# RcMPPT-Power_Module.net
KiCad netlist of a schematic drawn in Altium Designer
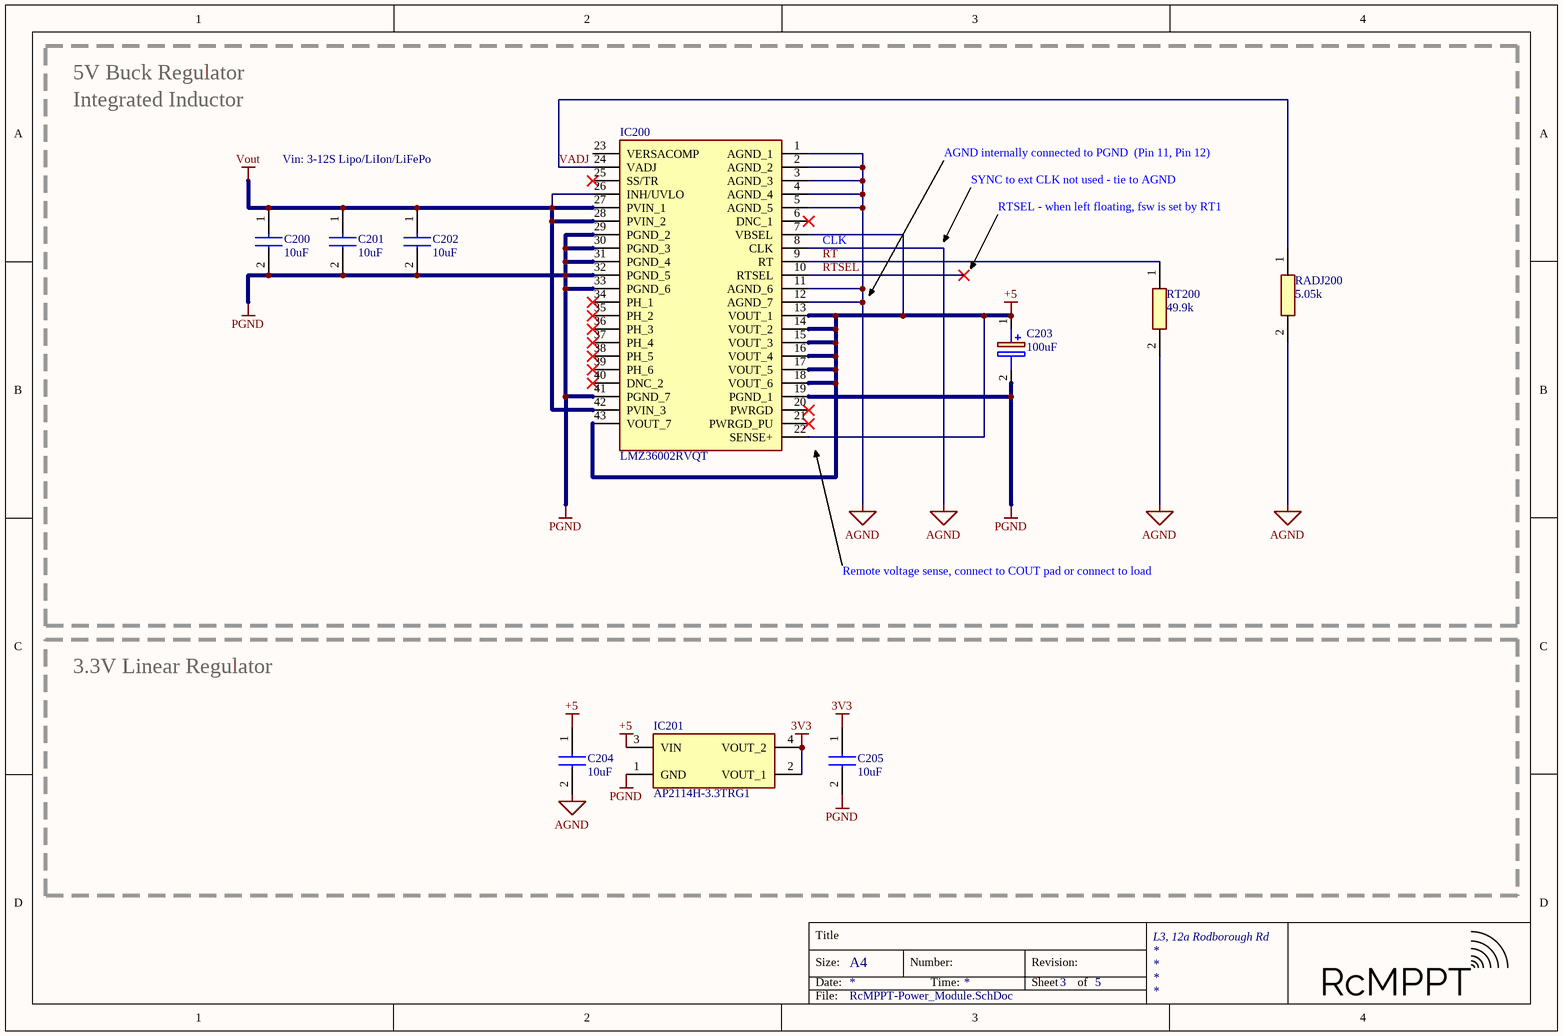
[diagram p0: RcMPPT-Power_Module.SchDoc]

(export (version "E")
  (design (tool "Eeschema 10.0.6"))
  (components
    (comp (ref "C200")
      (value "10uF")
      (footprint "RcMPPTLib:CAPC3225X280N")
      (description "Capacitor")
      (fields (field (name "MANUFACTURER_PART_NUMBER") "CL32B106KMVNNWE"))
      (libsource (lib "RcMPPTLib") (part "CL32B106KMVNNWE"))
    )
    (comp (ref "C201")
      (value "10uF")
      (footprint "RcMPPTLib:CAPC3225X280N")
      (description "Capacitor")
      (fields (field (name "MANUFACTURER_PART_NUMBER") "CL32B106KMVNNWE"))
      (libsource (lib "RcMPPTLib") (part "CL32B106KMVNNWE"))
    )
    (comp (ref "C202")
      (value "10uF")
      (footprint "RcMPPTLib:CAPC3225X280N")
      (description "Capacitor")
      (fields (field (name "MANUFACTURER_PART_NUMBER") "CL32B106KMVNNWE"))
      (libsource (lib "RcMPPTLib") (part "CL32B106KMVNNWE"))
    )
    (comp (ref "C203")
      (value "100uF")
      (footprint "CAPPM3528X200N")
      (description "Capacitor Polarised")
      (fields
        (field (name "MANUFACTURER_PART_NUMBER") "8TPE100MAZB")
        (field (name "MOUSER PART NUMBER") "667-8TPE100MAZB")
      )
      (libsource (lib "RcMPPTLib") (part "8TPE100MAZB"))
    )
    (comp (ref "C204")
      (value "10uF")
      (footprint "RcMPPTLib:CAPC3225X280N")
      (description "Capacitor")
      (fields (field (name "MANUFACTURER_PART_NUMBER") "CL32B106KMVNNWE"))
      (libsource (lib "RcMPPTLib") (part "CL32B106KMVNNWE"))
    )
    (comp (ref "C205")
      (value "10uF")
      (footprint "RcMPPTLib:CAPC3225X280N")
      (description "Capacitor")
      (fields (field (name "MANUFACTURER_PART_NUMBER") "CL32B106KMVNNWE"))
      (libsource (lib "RcMPPTLib") (part "CL32B106KMVNNWE"))
    )
    (comp (ref "IC200")
      (value "LMZ36002RVQT")
      (footprint "LMZ36002RVQR")
      (description "Integrated Circuit")
      (fields (field (name "MOUSER PART NUMBER") "595-LMZ36002RVQT"))
      (libsource (lib "RcMPPTLib") (part "LMZ36002RVQT"))
    )
    (comp (ref "IC201")
      (value "AP2114H-3.3TRG1")
      (footprint "SOT230P700X180-4N")
      (description "Integrated Circuit")
      (fields (field (name "MOUSER PART NUMBER") "621-AP2114H-3.3TRG1"))
      (libsource (lib "RcMPPTLib") (part "AP2114H-3.3TRG1"))
    )
    (comp (ref "RADJ200")
      (value "5.05k")
      (footprint "R0805")
      (description "Resistor")
      (fields
        (field (name "MANUFACTURER_PART_NUMBER") "RT0805BRD075K05L")
        (field (name "MOUSER PART NUMBER") "603-RT0805BRD075K05L")
      )
      (libsource (lib "RcMPPTLib") (part "RT0805BRD075K05L"))
    )
    (comp (ref "RT200")
      (value "49.9k")
      (footprint "RcMPPTLib:R0805")
      (description "Resistor")
      (fields
        (field (name "MANUFACTURER_PART_NUMBER") "ERJ-6ENF4992V")
        (field (name "MOUSER PART NUMBER") "667-ERJ-6ENF4992V")
      )
      (libsource (lib "RcMPPTLib") (part "ERJ-6ENF4992V"))
    )
  )
  (nets
    (net (code "1") (name "+5") (class "Default")
      (node (ref "C203") (pin "1") (pinfunction "+_1") (pintype "passive"))
      (node (ref "C204") (pin "1") (pinfunction "1_1") (pintype "passive"))
      (node (ref "IC200") (pin "13") (pinfunction "VOUT_1_13") (pintype "passive"))
      (node (ref "IC200") (pin "14") (pinfunction "VOUT_2_14") (pintype "passive"))
      (node (ref "IC200") (pin "15") (pinfunction "VOUT_3_15") (pintype "passive"))
      (node (ref "IC200") (pin "16") (pinfunction "VOUT_4_16") (pintype "passive"))
      (node (ref "IC200") (pin "17") (pinfunction "VOUT_5_17") (pintype "passive"))
      (node (ref "IC200") (pin "18") (pinfunction "VOUT_6_18") (pintype "passive"))
      (node (ref "IC200") (pin "22") (pinfunction "SENSE+_22") (pintype "passive"))
      (node (ref "IC200") (pin "43") (pinfunction "VOUT_7_43") (pintype "passive"))
      (node (ref "IC200") (pin "7") (pinfunction "VBSEL_7") (pintype "passive"))
      (node (ref "IC201") (pin "3") (pinfunction "VIN_3") (pintype "passive"))
    )
    (net (code "2") (name "/RT") (class "Default")
      (node (ref "IC200") (pin "9") (pinfunction "RT_9") (pintype "passive"))
      (node (ref "RT200") (pin "1") (pinfunction "1_1") (pintype "passive"))
    )
    (net (code "3") (name "/RTSEL") (class "Default")
      (node (ref "IC200") (pin "10") (pinfunction "RTSEL_10") (pintype "passive+no_connect"))
    )
    (net (code "4") (name "/VADJ") (class "Default")
      (node (ref "IC200") (pin "24") (pinfunction "VADJ_24") (pintype "passive"))
      (node (ref "RADJ200") (pin "1") (pinfunction "1_1") (pintype "passive"))
    )
    (net (code "5") (name "3V3") (class "Default")
      (node (ref "C205") (pin "1") (pinfunction "1_1") (pintype "passive"))
      (node (ref "IC201") (pin "2") (pinfunction "VOUT_1_2") (pintype "passive"))
      (node (ref "IC201") (pin "4") (pinfunction "VOUT_2_4") (pintype "passive"))
    )
    (net (code "6") (name "AGND") (class "Default")
      (node (ref "C204") (pin "2") (pinfunction "2_2") (pintype "passive"))
      (node (ref "IC200") (pin "1") (pinfunction "AGND_1_1") (pintype "passive"))
      (node (ref "IC200") (pin "11") (pinfunction "AGND_6_11") (pintype "passive"))
      (node (ref "IC200") (pin "12") (pinfunction "AGND_7_12") (pintype "passive"))
      (node (ref "IC200") (pin "2") (pinfunction "AGND_2_2") (pintype "passive"))
      (node (ref "IC200") (pin "3") (pinfunction "AGND_3_3") (pintype "passive"))
      (node (ref "IC200") (pin "4") (pinfunction "AGND_4_4") (pintype "passive"))
      (node (ref "IC200") (pin "5") (pinfunction "AGND_5_5") (pintype "passive"))
      (node (ref "IC200") (pin "8") (pinfunction "CLK_8") (pintype "passive"))
      (node (ref "RADJ200") (pin "2") (pinfunction "2_2") (pintype "passive"))
      (node (ref "RT200") (pin "2") (pinfunction "2_2") (pintype "passive"))
    )
    (net (code "7") (name "PGND") (class "Default")
      (node (ref "C200") (pin "2") (pinfunction "2_2") (pintype "passive"))
      (node (ref "C201") (pin "2") (pinfunction "2_2") (pintype "passive"))
      (node (ref "C202") (pin "2") (pinfunction "2_2") (pintype "passive"))
      (node (ref "C203") (pin "2") (pinfunction "-_2") (pintype "passive"))
      (node (ref "C205") (pin "2") (pinfunction "2_2") (pintype "passive"))
      (node (ref "IC200") (pin "19") (pinfunction "PGND_1_19") (pintype "passive"))
      (node (ref "IC200") (pin "29") (pinfunction "PGND_2_29") (pintype "passive"))
      (node (ref "IC200") (pin "30") (pinfunction "PGND_3_30") (pintype "passive"))
      (node (ref "IC200") (pin "31") (pinfunction "PGND_4_31") (pintype "passive"))
      (node (ref "IC200") (pin "32") (pinfunction "PGND_5_32") (pintype "passive"))
      (node (ref "IC200") (pin "33") (pinfunction "PGND_6_33") (pintype "passive"))
      (node (ref "IC200") (pin "41") (pinfunction "PGND_7_41") (pintype "passive"))
      (node (ref "IC201") (pin "1") (pinfunction "GND_1") (pintype "passive"))
    )
    (net (code "8") (name "Vout") (class "Default")
      (node (ref "C200") (pin "1") (pinfunction "1_1") (pintype "passive"))
      (node (ref "C201") (pin "1") (pinfunction "1_1") (pintype "passive"))
      (node (ref "C202") (pin "1") (pinfunction "1_1") (pintype "passive"))
      (node (ref "IC200") (pin "26") (pinfunction "INH/UVLO_26") (pintype "passive"))
      (node (ref "IC200") (pin "27") (pinfunction "PVIN_1_27") (pintype "passive"))
      (node (ref "IC200") (pin "28") (pinfunction "PVIN_2_28") (pintype "passive"))
      (node (ref "IC200") (pin "42") (pinfunction "PVIN_3_42") (pintype "passive"))
    )
    (net (code "9") (name "unconnected-(IC200-DNC_1-Pad6)") (class "Default")
      (node (ref "IC200") (pin "6") (pinfunction "DNC_1_6") (pintype "passive+no_connect"))
    )
    (net (code "10") (name "unconnected-(IC200-DNC_2-Pad40)") (class "Default")
      (node (ref "IC200") (pin "40") (pinfunction "DNC_2_40") (pintype "passive+no_connect"))
    )
    (net (code "11") (name "unconnected-(IC200-PH_1-Pad34)") (class "Default")
      (node (ref "IC200") (pin "34") (pinfunction "PH_1_34") (pintype "passive+no_connect"))
    )
    (net (code "12") (name "unconnected-(IC200-PH_2-Pad35)") (class "Default")
      (node (ref "IC200") (pin "35") (pinfunction "PH_2_35") (pintype "passive+no_connect"))
    )
    (net (code "13") (name "unconnected-(IC200-PH_3-Pad36)") (class "Default")
      (node (ref "IC200") (pin "36") (pinfunction "PH_3_36") (pintype "passive+no_connect"))
    )
    (net (code "14") (name "unconnected-(IC200-PH_4-Pad37)") (class "Default")
      (node (ref "IC200") (pin "37") (pinfunction "PH_4_37") (pintype "passive+no_connect"))
    )
    (net (code "15") (name "unconnected-(IC200-PH_5-Pad38)") (class "Default")
      (node (ref "IC200") (pin "38") (pinfunction "PH_5_38") (pintype "passive+no_connect"))
    )
    (net (code "16") (name "unconnected-(IC200-PH_6-Pad39)") (class "Default")
      (node (ref "IC200") (pin "39") (pinfunction "PH_6_39") (pintype "passive+no_connect"))
    )
    (net (code "17") (name "unconnected-(IC200-PWRGD-Pad20)") (class "Default")
      (node (ref "IC200") (pin "20") (pinfunction "PWRGD_20") (pintype "passive+no_connect"))
    )
    (net (code "18") (name "unconnected-(IC200-PWRGD_PU-Pad21)") (class "Default")
      (node (ref "IC200") (pin "21") (pinfunction "PWRGD_PU_21") (pintype "passive+no_connect"))
    )
    (net (code "19") (name "unconnected-(IC200-SS{slash}TR-Pad25)") (class "Default")
      (node (ref "IC200") (pin "25") (pinfunction "SS/TR_25") (pintype "passive+no_connect"))
    )
    (net (code "20") (name "unconnected-(IC200-VERSACOMP-Pad23)") (class "Default")
      (node (ref "IC200") (pin "23") (pinfunction "VERSACOMP_23") (pintype "passive"))
    )
  )
)
